# MiniGen.net
KiCad netlist of a schematic drawn in EAGLE
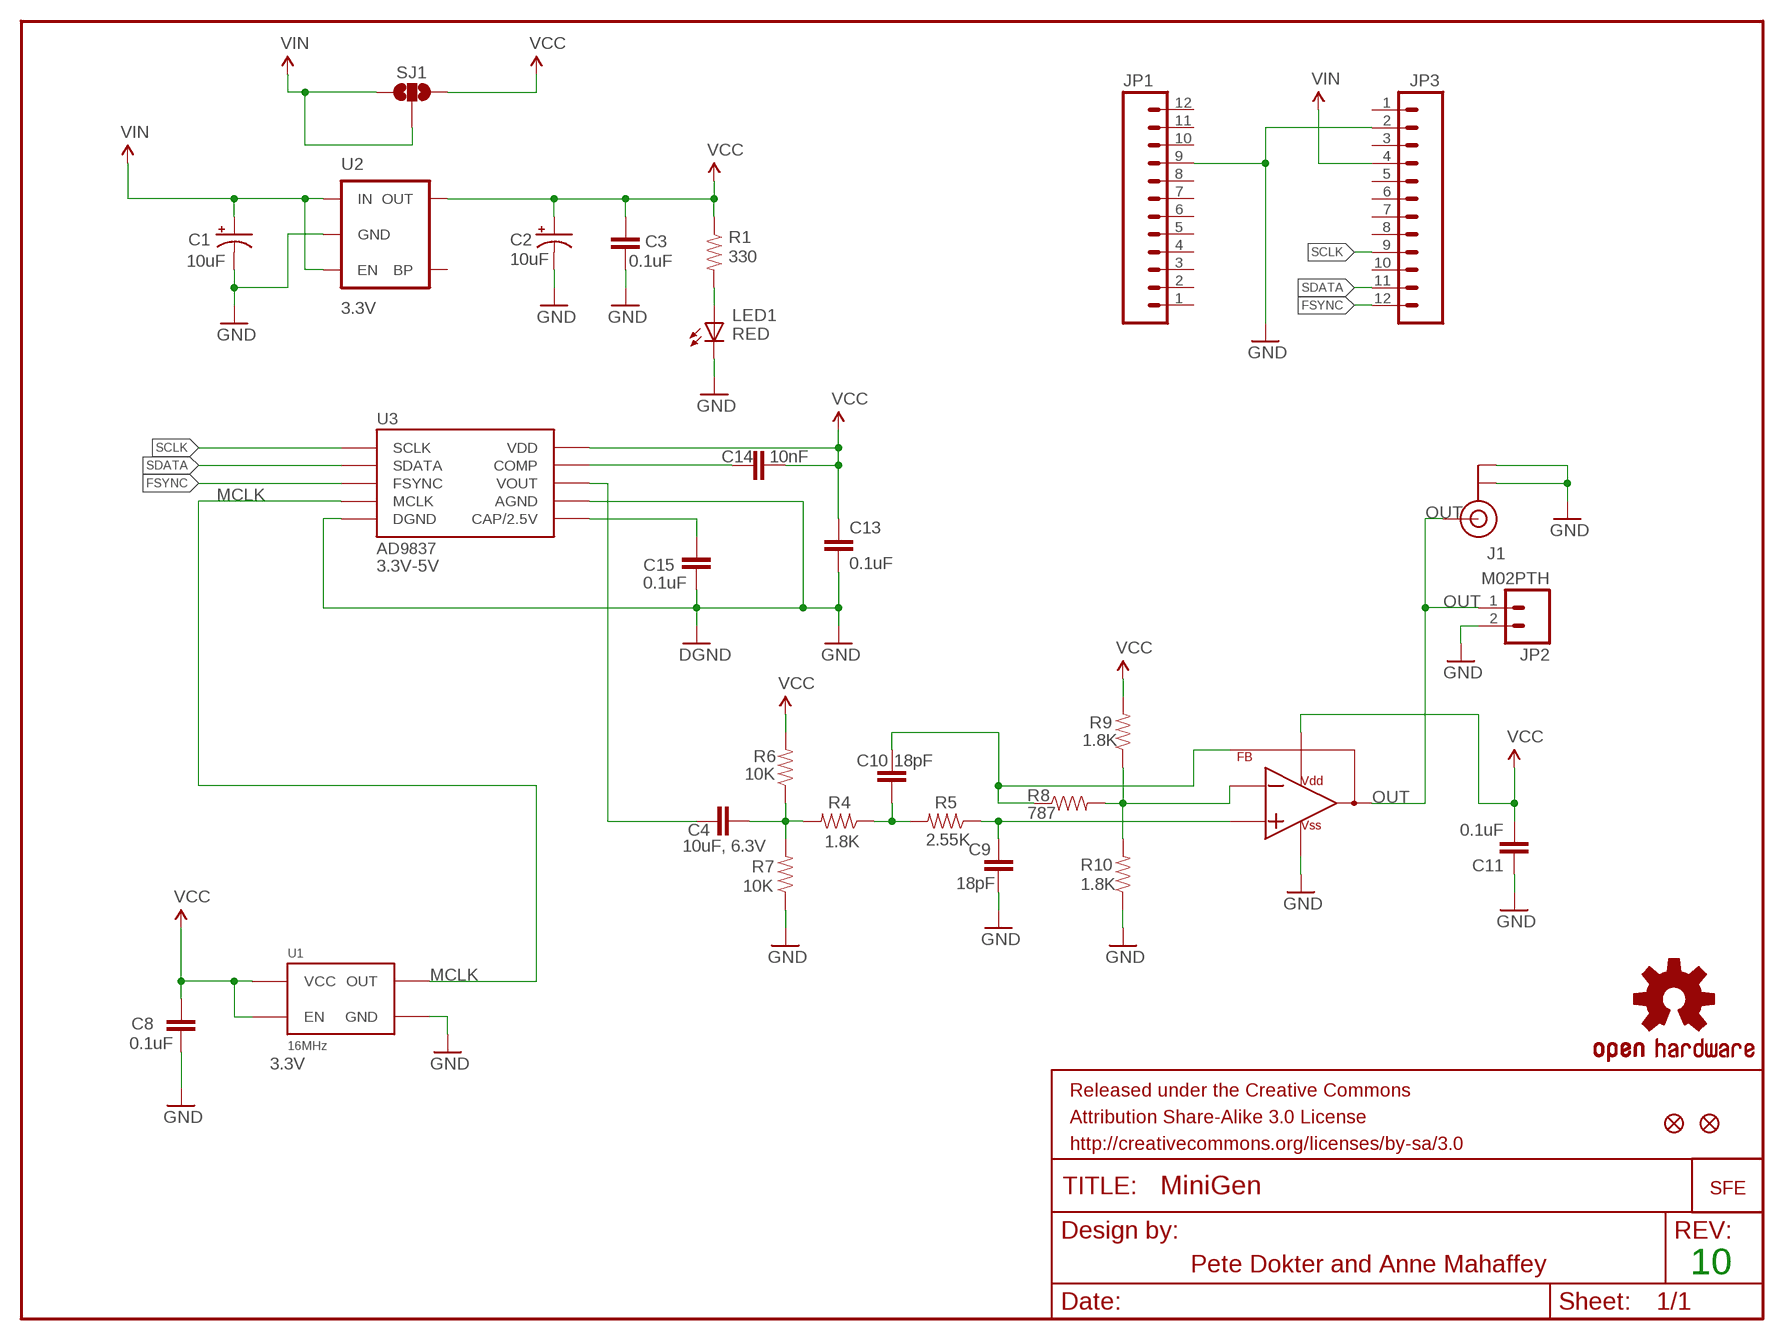
[diagram p0: schematic, sheet 1]

(export (version "E")
  (design (tool "Eeschema 10.0.6"))
  (components
    (comp (ref "C1")
      (value "10uF")
      (footprint "eagle-import:EIA3528")
      (libsource (lib "eagle-import") (part "10UF-20V-10%(TANT)"))
    )
    (comp (ref "C2")
      (value "10uF")
      (footprint "eagle-import:EIA3528")
      (libsource (lib "eagle-import") (part "10UF-20V-10%(TANT)"))
    )
    (comp (ref "C3")
      (value "0.1uF")
      (footprint "eagle-import:0603-CAP")
      (libsource (lib "eagle-import") (part "0.1UF-25V(+80/-20%)(0603)"))
    )
    (comp (ref "C4")
      (value "10uF, 6.3V")
      (footprint "eagle-import:0603-CAP")
      (libsource (lib "eagle-import") (part "10UF-6.3V-20%(0603)"))
    )
    (comp (ref "C8")
      (value "0.1uF")
      (footprint "eagle-import:0603-CAP")
      (libsource (lib "eagle-import") (part "0.1UF-25V(+80/-20%)(0603)"))
    )
    (comp (ref "C9")
      (value "18pF")
      (footprint "eagle-import:0603-CAP")
      (libsource (lib "eagle-import") (part "18PF-50V-5%(0603)"))
    )
    (comp (ref "C10")
      (value "18pF")
      (footprint "eagle-import:0603-CAP")
      (libsource (lib "eagle-import") (part "18PF-50V-5%(0603)"))
    )
    (comp (ref "C11")
      (value "0.1uF")
      (footprint "eagle-import:0603-CAP")
      (libsource (lib "eagle-import") (part "0.1UF-25V(+80/-20%)(0603)"))
    )
    (comp (ref "C13")
      (value "0.1uF")
      (footprint "eagle-import:0603-CAP")
      (libsource (lib "eagle-import") (part "0.1UF-25V(+80/-20%)(0603)"))
    )
    (comp (ref "C14")
      (value "10nF")
      (footprint "eagle-import:0603-CAP")
      (libsource (lib "eagle-import") (part "10NF/10000PF-50V-10%(0603)"))
    )
    (comp (ref "C15")
      (value "0.1uF")
      (footprint "eagle-import:0603-CAP")
      (libsource (lib "eagle-import") (part "0.1UF-25V(+80/-20%)(0603)"))
    )
    (comp (ref "FID1")
      (value "FIDUCIAL1X2")
      (footprint "eagle-import:FIDUCIAL-1X2")
      (libsource (lib "eagle-import") (part "FIDUCIAL1X2"))
    )
    (comp (ref "FID2")
      (value "FIDUCIAL1X2")
      (footprint "eagle-import:FIDUCIAL-1X2")
      (libsource (lib "eagle-import") (part "FIDUCIAL1X2"))
    )
    (comp (ref "FRAME1")
      (value "FRAME-LETTER")
      (footprint "eagle-import:CREATIVE_COMMONS")
      (libsource (lib "eagle-import") (part "FRAME-LETTER"))
    )
    (comp (ref "J1")
      (value "U.FL")
      (footprint "eagle-import:U.FL")
      (libsource (lib "eagle-import") (part "U.FL"))
    )
    (comp (ref "JP1")
      (value "M12PTH")
      (footprint "eagle-import:1X12")
      (libsource (lib "eagle-import") (part "M12PTH"))
    )
    (comp (ref "JP2")
      (value "M02PTH")
      (footprint "eagle-import:1X02")
      (libsource (lib "eagle-import") (part "M02PTH"))
    )
    (comp (ref "JP3")
      (value "M12PTH")
      (footprint "eagle-import:1X12")
      (libsource (lib "eagle-import") (part "M12PTH"))
    )
    (comp (ref "JP4")
      (value "LOGO-SFENEW")
      (footprint "eagle-import:SFE-NEW-WEBLOGO")
      (libsource (lib "eagle-import") (part "LOGO-SFENEW"))
    )
    (comp (ref "LED1")
      (value "RED")
      (footprint "eagle-import:LED-0603")
      (libsource (lib "eagle-import") (part "LED-RED0603"))
    )
    (comp (ref "R1")
      (value "330")
      (footprint "eagle-import:0603-RES")
      (libsource (lib "eagle-import") (part "330OHM1/10W1%(0603)"))
    )
    (comp (ref "R4")
      (value "1.8K")
      (footprint "eagle-import:0603-RES")
      (libsource (lib "eagle-import") (part "1.8KOHM1/10W1%(0603)"))
    )
    (comp (ref "R5")
      (value "2.55K")
      (footprint "eagle-import:0603-RES")
      (libsource (lib "eagle-import") (part "2.55KOHM-1/10W-1%(0603)"))
    )
    (comp (ref "R6")
      (value "10K")
      (footprint "eagle-import:0603-RES")
      (libsource (lib "eagle-import") (part "10KOHM1/10W1%(0603)0603"))
    )
    (comp (ref "R7")
      (value "10K")
      (footprint "eagle-import:0603-RES")
      (libsource (lib "eagle-import") (part "10KOHM1/10W1%(0603)0603"))
    )
    (comp (ref "R8")
      (value "787")
      (footprint "eagle-import:0603-RES")
      (libsource (lib "eagle-import") (part "787-1%"))
    )
    (comp (ref "R9")
      (value "1.8K")
      (footprint "eagle-import:0603-RES")
      (libsource (lib "eagle-import") (part "1.8KOHM1/10W1%(0603)"))
    )
    (comp (ref "R10")
      (value "1.8K")
      (footprint "eagle-import:0603-RES")
      (libsource (lib "eagle-import") (part "1.8KOHM1/10W1%(0603)"))
    )
    (comp (ref "SJ1")
      (value "SOLDERJUMPER_2WAYT")
      (footprint "eagle-import:SJ_2")
      (libsource (lib "eagle-import") (part "SOLDERJUMPER_2WAYT"))
    )
    (comp (ref "U$2")
      (value "OSHW-LOGOS")
      (footprint "eagle-import:OSHW-LOGO-S")
      (libsource (lib "eagle-import") (part "OSHW-LOGOS"))
    )
    (comp (ref "U1")
      (value "16MHz")
      (footprint "eagle-import:CRYSTAL-SMD-7X5")
      (libsource (lib "eagle-import") (part "OSCILLATORXTAL-11225"))
    )
    (comp (ref "U2")
      (value "3.3V")
      (footprint "eagle-import:SOT23-5")
      (libsource (lib "eagle-import") (part "MIC52053.3V"))
    )
    (comp (ref "U3")
      (value "AD9837")
      (footprint "eagle-import:AD9837")
      (libsource (lib "eagle-import") (part "AD9837"))
    )
    (comp (ref "U4")
      (value "ADC8045")
      (footprint "eagle-import:SO08")
      (libsource (lib "eagle-import") (part "ADC8045"))
    )
  )
  (nets
    (net (code "1") (name "/MCLK") (class "Default")
      (node (ref "U1") (pin "P$3") (pinfunction "OUT_P$3") (pintype "bidirectional"))
      (node (ref "U3") (pin "P$5") (pinfunction "MCLK_P$5") (pintype "bidirectional"))
    )
    (net (code "2") (name "/OUT") (class "Default")
      (node (ref "J1") (pin "P$3") (pinfunction "SIGNAL_P$3") (pintype "bidirectional"))
      (node (ref "JP2") (pin "1") (pinfunction "1_1") (pintype "passive"))
      (node (ref "U4") (pin "6") (pinfunction "OUT_6") (pintype "bidirectional"))
    )
    (net (code "3") (name "DGND") (class "Default")
      (node (ref "C1") (pin "C") (pinfunction "-_C") (pintype "passive"))
      (node (ref "C11") (pin "1") (pinfunction "1_1") (pintype "passive"))
      (node (ref "C13") (pin "2") (pinfunction "2_2") (pintype "passive"))
      (node (ref "C15") (pin "2") (pinfunction "2_2") (pintype "passive"))
      (node (ref "C2") (pin "C") (pinfunction "-_C") (pintype "passive"))
      (node (ref "C3") (pin "2") (pinfunction "2_2") (pintype "passive"))
      (node (ref "C8") (pin "2") (pinfunction "2_2") (pintype "passive"))
      (node (ref "C9") (pin "1") (pinfunction "1_1") (pintype "passive"))
      (node (ref "J1") (pin "P$1") (pinfunction "GND_P$1") (pintype "bidirectional"))
      (node (ref "J1") (pin "P$2") (pinfunction "GND_P$2") (pintype "bidirectional"))
      (node (ref "JP1") (pin "9") (pinfunction "9_9") (pintype "passive"))
      (node (ref "JP2") (pin "2") (pinfunction "2_2") (pintype "passive"))
      (node (ref "JP3") (pin "2") (pinfunction "2_2") (pintype "passive"))
      (node (ref "LED1") (pin "C") (pinfunction "C_C") (pintype "passive"))
      (node (ref "R10") (pin "1") (pinfunction "1_1") (pintype "passive"))
      (node (ref "R7") (pin "1") (pinfunction "1_1") (pintype "passive"))
      (node (ref "U1") (pin "P$2") (pinfunction "GND_P$2") (pintype "bidirectional"))
      (node (ref "U2") (pin "2") (pinfunction "GND_2") (pintype "input"))
      (node (ref "U3") (pin "P$0") (pinfunction "DGND_P$0") (pintype "bidirectional"))
      (node (ref "U3") (pin "P$4") (pinfunction "DGND_P$4") (pintype "bidirectional"))
      (node (ref "U3") (pin "P$9") (pinfunction "AGND_P$9") (pintype "bidirectional"))
      (node (ref "U4") (pin "4") (pinfunction "VSS_4") (pintype "bidirectional"))
    )
    (net (code "4") (name "FSYNC") (class "Default")
      (node (ref "JP3") (pin "12") (pinfunction "12_12") (pintype "passive"))
      (node (ref "U3") (pin "P$8") (pinfunction "FSYNC_P$8") (pintype "bidirectional"))
    )
    (net (code "5") (name "Net-(C4-Pad2)") (class "Default")
      (node (ref "C4") (pin "2") (pinfunction "2_2") (pintype "passive"))
      (node (ref "R4") (pin "2") (pinfunction "2_2") (pintype "passive"))
      (node (ref "R6") (pin "1") (pinfunction "1_1") (pintype "passive"))
      (node (ref "R7") (pin "2") (pinfunction "2_2") (pintype "passive"))
    )
    (net (code "6") (name "Net-(C10-Pad1)") (class "Default")
      (node (ref "C10") (pin "1") (pinfunction "1_1") (pintype "passive"))
      (node (ref "R4") (pin "1") (pinfunction "1_1") (pintype "passive"))
      (node (ref "R5") (pin "2") (pinfunction "2_2") (pintype "passive"))
    )
    (net (code "7") (name "Net-(LED1-PadA)") (class "Default")
      (node (ref "LED1") (pin "A") (pinfunction "A_A") (pintype "passive"))
      (node (ref "R1") (pin "2") (pinfunction "2_2") (pintype "passive"))
    )
    (net (code "8") (name "Net-(U3-CAP{slash}2.5V)") (class "Default")
      (node (ref "C15") (pin "1") (pinfunction "1_1") (pintype "passive"))
      (node (ref "U3") (pin "P$3") (pinfunction "CAP/2.5V_P$3") (pintype "bidirectional"))
    )
    (net (code "9") (name "Net-(U3-COMP)") (class "Default")
      (node (ref "C14") (pin "1") (pinfunction "1_1") (pintype "passive"))
      (node (ref "U3") (pin "P$1") (pinfunction "COMP_P$1") (pintype "bidirectional"))
    )
    (net (code "10") (name "Net-(U3-VOUT)") (class "Default")
      (node (ref "C4") (pin "1") (pinfunction "1_1") (pintype "passive"))
      (node (ref "U3") (pin "P$10") (pinfunction "VOUT_P$10") (pintype "bidirectional"))
    )
    (net (code "11") (name "Net-(U4-FB)") (class "Default")
      (node (ref "C10") (pin "2") (pinfunction "2_2") (pintype "passive"))
      (node (ref "R8") (pin "1") (pinfunction "1_1") (pintype "passive"))
      (node (ref "U4") (pin "1") (pinfunction "FB_1") (pintype "bidirectional"))
    )
    (net (code "12") (name "Net-(U4-IN+)") (class "Default")
      (node (ref "C9") (pin "2") (pinfunction "2_2") (pintype "passive"))
      (node (ref "R5") (pin "1") (pinfunction "1_1") (pintype "passive"))
      (node (ref "U4") (pin "3") (pinfunction "IN+_3") (pintype "bidirectional"))
    )
    (net (code "13") (name "Net-(U4-IN-)") (class "Default")
      (node (ref "R10") (pin "2") (pinfunction "2_2") (pintype "passive"))
      (node (ref "R8") (pin "2") (pinfunction "2_2") (pintype "passive"))
      (node (ref "R9") (pin "1") (pinfunction "1_1") (pintype "passive"))
      (node (ref "U4") (pin "2") (pinfunction "IN-_2") (pintype "bidirectional"))
    )
    (net (code "14") (name "SCLK") (class "Default")
      (node (ref "JP3") (pin "9") (pinfunction "9_9") (pintype "passive"))
      (node (ref "U3") (pin "P$7") (pinfunction "SCLK_P$7") (pintype "bidirectional"))
    )
    (net (code "15") (name "SDATA") (class "Default")
      (node (ref "JP3") (pin "11") (pinfunction "11_11") (pintype "passive"))
      (node (ref "U3") (pin "P$6") (pinfunction "SDATA_P$6") (pintype "bidirectional"))
    )
    (net (code "16") (name "VCC") (class "Default")
      (node (ref "C11") (pin "2") (pinfunction "2_2") (pintype "passive"))
      (node (ref "C13") (pin "1") (pinfunction "1_1") (pintype "passive"))
      (node (ref "C14") (pin "2") (pinfunction "2_2") (pintype "passive"))
      (node (ref "C2") (pin "A") (pinfunction "+_A") (pintype "passive"))
      (node (ref "C3") (pin "1") (pinfunction "1_1") (pintype "passive"))
      (node (ref "C8") (pin "1") (pinfunction "1_1") (pintype "passive"))
      (node (ref "R1") (pin "1") (pinfunction "1_1") (pintype "passive"))
      (node (ref "R6") (pin "2") (pinfunction "2_2") (pintype "passive"))
      (node (ref "R9") (pin "2") (pinfunction "2_2") (pintype "passive"))
      (node (ref "SJ1") (pin "3") (pinfunction "3_3") (pintype "passive"))
      (node (ref "U1") (pin "P$1") (pinfunction "EN_P$1") (pintype "bidirectional"))
      (node (ref "U1") (pin "P$4") (pinfunction "VCC_P$4") (pintype "bidirectional"))
      (node (ref "U2") (pin "5") (pinfunction "OUT_5") (pintype "passive"))
      (node (ref "U3") (pin "P$2") (pinfunction "VDD_P$2") (pintype "bidirectional"))
      (node (ref "U4") (pin "7") (pinfunction "VDD_7") (pintype "bidirectional"))
    )
    (net (code "17") (name "VIN") (class "Default")
      (node (ref "C1") (pin "A") (pinfunction "+_A") (pintype "passive"))
      (node (ref "JP3") (pin "4") (pinfunction "4_4") (pintype "passive"))
      (node (ref "SJ1") (pin "1") (pinfunction "1_1") (pintype "passive"))
      (node (ref "SJ1") (pin "2") (pinfunction "2_2") (pintype "passive"))
      (node (ref "U2") (pin "1") (pinfunction "IN_1") (pintype "input"))
      (node (ref "U2") (pin "3") (pinfunction "EN_3") (pintype "input"))
    )
    (net (code "18") (name "unconnected-(JP1-Pad1)") (class "Default")
      (node (ref "JP1") (pin "1") (pinfunction "1_1") (pintype "passive"))
    )
    (net (code "19") (name "unconnected-(JP1-Pad2)") (class "Default")
      (node (ref "JP1") (pin "2") (pinfunction "2_2") (pintype "passive"))
    )
    (net (code "20") (name "unconnected-(JP1-Pad3)") (class "Default")
      (node (ref "JP1") (pin "3") (pinfunction "3_3") (pintype "passive"))
    )
    (net (code "21") (name "unconnected-(JP1-Pad4)") (class "Default")
      (node (ref "JP1") (pin "4") (pinfunction "4_4") (pintype "passive"))
    )
    (net (code "22") (name "unconnected-(JP1-Pad5)") (class "Default")
      (node (ref "JP1") (pin "5") (pinfunction "5_5") (pintype "passive"))
    )
    (net (code "23") (name "unconnected-(JP1-Pad6)") (class "Default")
      (node (ref "JP1") (pin "6") (pinfunction "6_6") (pintype "passive"))
    )
    (net (code "24") (name "unconnected-(JP1-Pad7)") (class "Default")
      (node (ref "JP1") (pin "7") (pinfunction "7_7") (pintype "passive"))
    )
    (net (code "25") (name "unconnected-(JP1-Pad8)") (class "Default")
      (node (ref "JP1") (pin "8") (pinfunction "8_8") (pintype "passive"))
    )
    (net (code "26") (name "unconnected-(JP1-Pad10)") (class "Default")
      (node (ref "JP1") (pin "10") (pinfunction "10_10") (pintype "passive"))
    )
    (net (code "27") (name "unconnected-(JP1-Pad11)") (class "Default")
      (node (ref "JP1") (pin "11") (pinfunction "11_11") (pintype "passive"))
    )
    (net (code "28") (name "unconnected-(JP1-Pad12)") (class "Default")
      (node (ref "JP1") (pin "12") (pinfunction "12_12") (pintype "passive"))
    )
    (net (code "29") (name "unconnected-(JP3-Pad1)") (class "Default")
      (node (ref "JP3") (pin "1") (pinfunction "1_1") (pintype "passive"))
    )
    (net (code "30") (name "unconnected-(JP3-Pad3)") (class "Default")
      (node (ref "JP3") (pin "3") (pinfunction "3_3") (pintype "passive"))
    )
    (net (code "31") (name "unconnected-(JP3-Pad5)") (class "Default")
      (node (ref "JP3") (pin "5") (pinfunction "5_5") (pintype "passive"))
    )
    (net (code "32") (name "unconnected-(JP3-Pad6)") (class "Default")
      (node (ref "JP3") (pin "6") (pinfunction "6_6") (pintype "passive"))
    )
    (net (code "33") (name "unconnected-(JP3-Pad7)") (class "Default")
      (node (ref "JP3") (pin "7") (pinfunction "7_7") (pintype "passive"))
    )
    (net (code "34") (name "unconnected-(JP3-Pad8)") (class "Default")
      (node (ref "JP3") (pin "8") (pinfunction "8_8") (pintype "passive"))
    )
    (net (code "35") (name "unconnected-(JP3-Pad10)") (class "Default")
      (node (ref "JP3") (pin "10") (pinfunction "10_10") (pintype "passive"))
    )
    (net (code "36") (name "unconnected-(U2-BP-Pad4)") (class "Default")
      (node (ref "U2") (pin "4") (pinfunction "BP_4") (pintype "input"))
    )
  )
)
